# STPMXX.net
KiCad netlist of a schematic drawn in Altium Designer
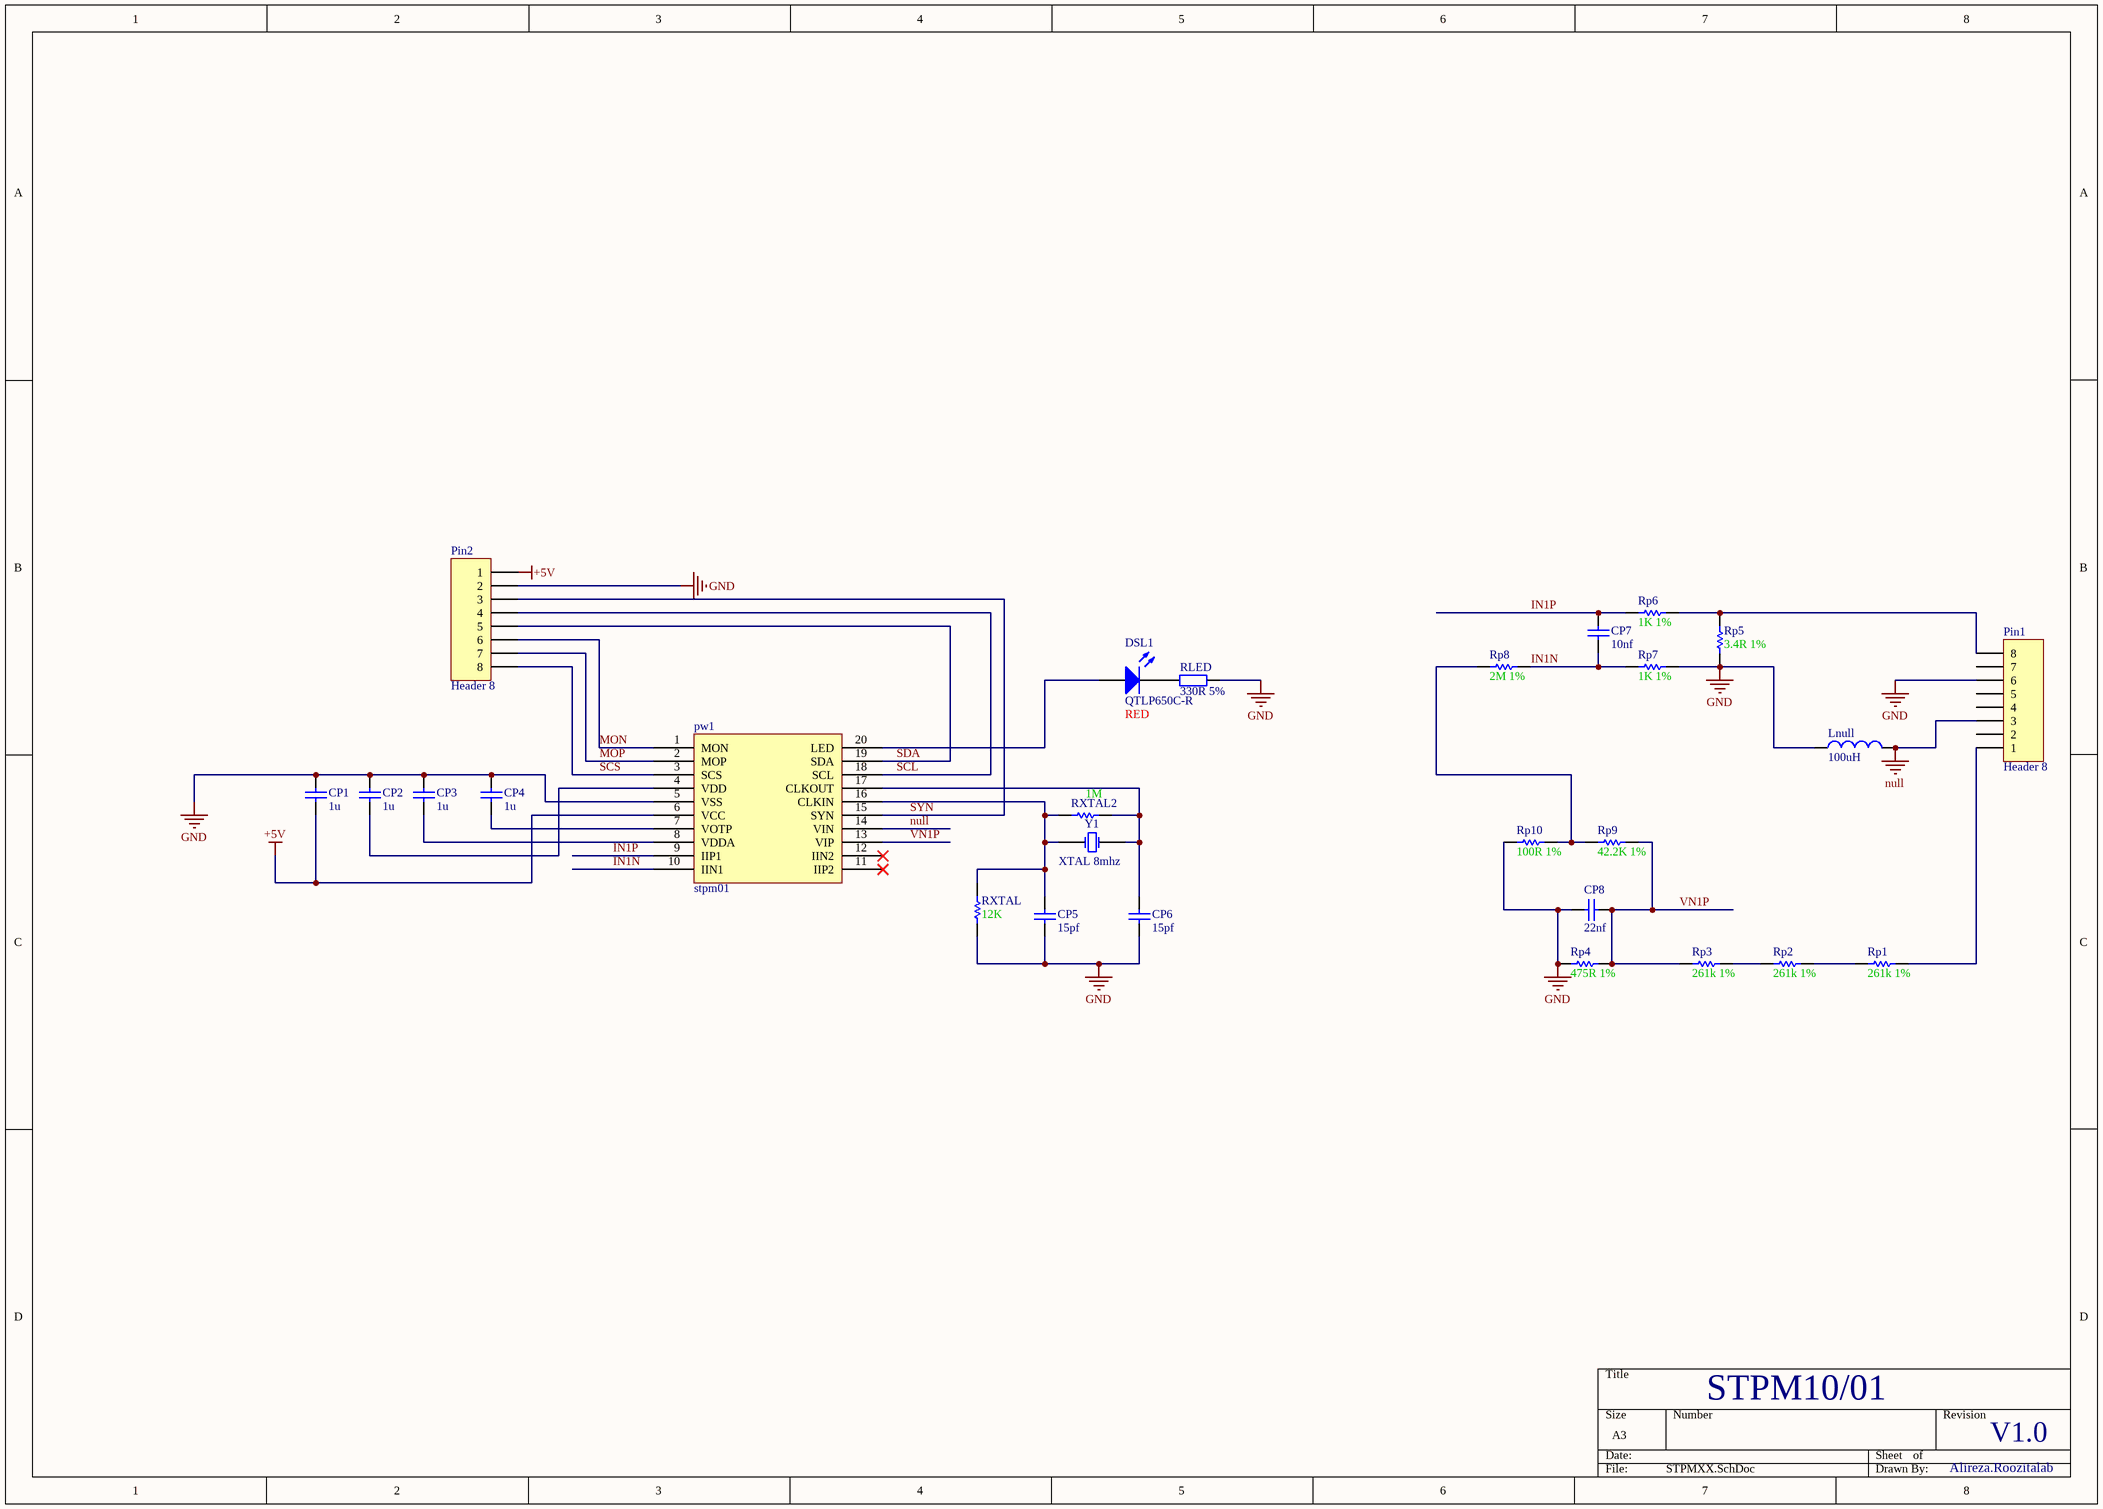
[diagram p0: STPMXX.SchDoc]

(export (version "E")
  (design (tool "Eeschema 10.0.6"))
  (components
    (comp (ref "CP1")
      (value "1u")
      (footprint "CAP 1206 (3216X08L)")
      (description "Capacitor")
      (fields (field (name "Comment") "Cap") (field (name "PUBLISHER") "Altium Limited"))
      (libsource (lib "alarmboxv2") (part "Cap"))
    )
    (comp (ref "CP2")
      (value "1u")
      (footprint "CAP 1206 (3216X08L)")
      (description "Capacitor")
      (fields (field (name "Comment") "Cap") (field (name "PUBLISHER") "Altium Limited"))
      (libsource (lib "alarmboxv2") (part "Cap"))
    )
    (comp (ref "CP3")
      (value "1u")
      (footprint "CAP 1206 (3216X08L)")
      (description "Capacitor")
      (fields (field (name "Comment") "Cap") (field (name "PUBLISHER") "Altium Limited"))
      (libsource (lib "alarmboxv2") (part "Cap"))
    )
    (comp (ref "CP4")
      (value "1u")
      (footprint "CAP 1206 (3216X08L)")
      (description "Capacitor")
      (fields (field (name "Comment") "Cap") (field (name "PUBLISHER") "Altium Limited"))
      (libsource (lib "alarmboxv2") (part "Cap"))
    )
    (comp (ref "CP5")
      (value "15pf")
      (footprint "CAP 1206 (3216X08L)")
      (description "Capacitor")
      (fields (field (name "Comment") "Cap") (field (name "PUBLISHER") "Altium Limited"))
      (libsource (lib "alarmboxv2") (part "Cap"))
    )
    (comp (ref "CP6")
      (value "15pf")
      (footprint "CAP 1206 (3216X08L)")
      (description "Capacitor")
      (fields (field (name "Comment") "Cap") (field (name "PUBLISHER") "Altium Limited"))
      (libsource (lib "alarmboxv2") (part "Cap"))
    )
    (comp (ref "CP7")
      (value "10nf")
      (footprint "CAP 1206 (3216X08L)")
      (description "Capacitor")
      (fields (field (name "Comment") "Cap") (field (name "PUBLISHER") "Altium Limited"))
      (libsource (lib "alarmboxv2") (part "Cap"))
    )
    (comp (ref "CP8")
      (value "22nf")
      (footprint "CAP 1206 (3216X08L)")
      (description "Capacitor")
      (fields (field (name "Comment") "Cap") (field (name "PUBLISHER") "Altium Limited"))
      (libsource (lib "alarmboxv2") (part "Cap"))
    )
    (comp (ref "DSL1")
      (value "QTLP650C-R")
      (footprint "led-1206")
      (description "Typical INFRARED GaAs LED")
      (fields (field (name "ALTIUM_VALUE") "RED") (field (name "PUBLISHER") "Altium Limited"))
      (libsource (lib "alarmboxv2") (part "LED0_1"))
    )
    (comp (ref "Lnull")
      (value "100uH")
      (footprint "INDUCTOR-1206")
      (description "Inductor")
      (fields (field (name "PUBLISHER") "Altium Limited"))
      (libsource (lib "alarmboxv2") (part "Inductor_1"))
    )
    (comp (ref "Pin1")
      (value "Header 8")
      (footprint "HDR1X8")
      (description "Header, 8-Pin")
      (fields (field (name "PUBLISHER") "Altium Limited"))
      (libsource (lib "") (part "Header 8_1"))
    )
    (comp (ref "Pin2")
      (value "Header 8")
      (footprint "HDR1X8")
      (description "Header, 8-Pin")
      (fields (field (name "PUBLISHER") "Altium Limited"))
      (libsource (lib "Miscellaneous Connectors") (part "Header 8"))
    )
    (comp (ref "pw1") (value "stpm01") (footprint "TSSOP") (libsource (lib "armlib") (part "stpm01")))
    (comp (ref "RLED")
      (value "330R 5%")
      (footprint "RES 1206 (3216X08L)")
      (description "Resistor")
      (fields (field (name "Comment") "Res2") (field (name "PUBLISHER") "Altium Limited"))
      (libsource (lib "alarmboxv2") (part "Res2_1"))
    )
    (comp (ref "Rp1")
      (value "261k 1%")
      (footprint "RES 1206 (3216X08L)")
      (description "Semiconductor Resistor")
      (fields (field (name "Comment") "Res Semi") (field (name "PUBLISHER") "Altium Limited"))
      (libsource (lib "alarmboxv2") (part "Res Semi"))
    )
    (comp (ref "Rp2")
      (value "261k 1%")
      (footprint "RES 1206 (3216X08L)")
      (description "Semiconductor Resistor")
      (fields (field (name "Comment") "Res Semi") (field (name "PUBLISHER") "Altium Limited"))
      (libsource (lib "alarmboxv2") (part "Res Semi"))
    )
    (comp (ref "Rp3")
      (value "261k 1%")
      (footprint "RES 1206 (3216X08L)")
      (description "Semiconductor Resistor")
      (fields (field (name "Comment") "Res Semi") (field (name "PUBLISHER") "Altium Limited"))
      (libsource (lib "alarmboxv2") (part "Res Semi"))
    )
    (comp (ref "Rp4")
      (value "475R 1%")
      (footprint "RES 1206 (3216X08L)")
      (description "Semiconductor Resistor")
      (fields (field (name "Comment") "Res Semi") (field (name "PUBLISHER") "Altium Limited"))
      (libsource (lib "alarmboxv2") (part "Res Semi"))
    )
    (comp (ref "Rp5")
      (value "3.4R 1%")
      (footprint "RES 1206 (3216X08L)")
      (description "Semiconductor Resistor")
      (fields (field (name "Comment") "Res Semi") (field (name "PUBLISHER") "Altium Limited"))
      (libsource (lib "alarmboxv2") (part "Res Semi"))
    )
    (comp (ref "Rp6")
      (value "1K 1%")
      (footprint "RES 1206 (3216X08L)")
      (description "Semiconductor Resistor")
      (fields (field (name "Comment") "Res Semi") (field (name "PUBLISHER") "Altium Limited"))
      (libsource (lib "alarmboxv2") (part "Res Semi"))
    )
    (comp (ref "Rp7")
      (value "1K 1%")
      (footprint "RES 1206 (3216X08L)")
      (description "Semiconductor Resistor")
      (fields (field (name "Comment") "Res Semi") (field (name "PUBLISHER") "Altium Limited"))
      (libsource (lib "alarmboxv2") (part "Res Semi"))
    )
    (comp (ref "Rp8")
      (value "2M 1%")
      (footprint "RES 1206 (3216X08L)")
      (description "Semiconductor Resistor")
      (fields (field (name "Comment") "Res Semi") (field (name "PUBLISHER") "Altium Limited"))
      (libsource (lib "alarmboxv2") (part "Res Semi"))
    )
    (comp (ref "Rp9")
      (value "42.2K 1%")
      (footprint "RES 1206 (3216X08L)")
      (description "Semiconductor Resistor")
      (fields (field (name "Comment") "Res Semi") (field (name "PUBLISHER") "Altium Limited"))
      (libsource (lib "alarmboxv2") (part "Res Semi"))
    )
    (comp (ref "Rp10")
      (value "100R 1%")
      (footprint "RES 1206 (3216X08L)")
      (description "Semiconductor Resistor")
      (fields (field (name "Comment") "Res Semi") (field (name "PUBLISHER") "Altium Limited"))
      (libsource (lib "alarmboxv2") (part "Res Semi"))
    )
    (comp (ref "RXTAL")
      (value "12K")
      (footprint "RES 1206 (3216X08L)")
      (description "Semiconductor Resistor")
      (fields (field (name "Comment") "Res Semi") (field (name "PUBLISHER") "Altium Limited"))
      (libsource (lib "alarmboxv2") (part "Res Semi"))
    )
    (comp (ref "RXTAL2")
      (value "1M")
      (footprint "RES 1206 (3216X08L)")
      (description "Semiconductor Resistor")
      (fields (field (name "Comment") "Res Semi") (field (name "PUBLISHER") "Altium Limited"))
      (libsource (lib "alarmboxv2") (part "Res Semi"))
    )
    (comp (ref "Y1")
      (value "XTAL 8mhz")
      (footprint "XTAL SMALL")
      (description "Crystal Oscillator")
      (fields (field (name "PUBLISHER") "Altium Limited"))
      (libsource (lib "alarmboxv2") (part "XTAL"))
    )
  )
  (nets
    (net (code "1") (name "+5V") (class "Default")
      (node (ref "CP1") (pin "1") (pinfunction "1_1") (pintype "passive"))
      (node (ref "Pin2") (pin "1") (pinfunction "1_1") (pintype "passive"))
      (node (ref "pw1") (pin "6") (pinfunction "VCC_6") (pintype "passive"))
    )
    (net (code "2") (name "/IN1N") (class "Default")
      (node (ref "CP7") (pin "1") (pinfunction "1_1") (pintype "passive"))
      (node (ref "Rp7") (pin "1") (pinfunction "1_1") (pintype "passive"))
      (node (ref "Rp8") (pin "2") (pinfunction "2_2") (pintype "passive"))
      (node (ref "pw1") (pin "10") (pinfunction "IIN1_10") (pintype "passive"))
    )
    (net (code "3") (name "/IN1P") (class "Default")
      (node (ref "CP7") (pin "2") (pinfunction "2_2") (pintype "passive"))
      (node (ref "Rp6") (pin "1") (pinfunction "1_1") (pintype "passive"))
      (node (ref "pw1") (pin "9") (pinfunction "IIP1_9") (pintype "passive"))
    )
    (net (code "4") (name "/MON") (class "Default")
      (node (ref "Pin2") (pin "6") (pinfunction "6_6") (pintype "passive"))
      (node (ref "pw1") (pin "1") (pinfunction "MON_1") (pintype "passive"))
    )
    (net (code "5") (name "/MOP") (class "Default")
      (node (ref "Pin2") (pin "7") (pinfunction "7_7") (pintype "passive"))
      (node (ref "pw1") (pin "2") (pinfunction "MOP_2") (pintype "passive"))
    )
    (net (code "6") (name "/SCL") (class "Default")
      (node (ref "Pin2") (pin "4") (pinfunction "4_4") (pintype "passive"))
      (node (ref "pw1") (pin "18") (pinfunction "SCL_18") (pintype "passive"))
    )
    (net (code "7") (name "/SCS") (class "Default")
      (node (ref "Pin2") (pin "8") (pinfunction "8_8") (pintype "passive"))
      (node (ref "pw1") (pin "3") (pinfunction "SCS_3") (pintype "passive"))
    )
    (net (code "8") (name "/SDA") (class "Default")
      (node (ref "Pin2") (pin "5") (pinfunction "5_5") (pintype "passive"))
      (node (ref "pw1") (pin "19") (pinfunction "SDA_19") (pintype "passive"))
    )
    (net (code "9") (name "/SYN") (class "Default")
      (node (ref "Pin2") (pin "3") (pinfunction "3_3") (pintype "passive"))
      (node (ref "pw1") (pin "15") (pinfunction "SYN_15") (pintype "passive"))
    )
    (net (code "10") (name "/VN1P") (class "Default")
      (node (ref "CP8") (pin "1") (pinfunction "1_1") (pintype "passive"))
      (node (ref "Rp3") (pin "2") (pinfunction "2_2") (pintype "passive"))
      (node (ref "Rp4") (pin "1") (pinfunction "1_1") (pintype "passive"))
      (node (ref "Rp9") (pin "2") (pinfunction "2_2") (pintype "passive"))
      (node (ref "pw1") (pin "13") (pinfunction "VIP_13") (pintype "passive"))
    )
    (net (code "11") (name "GND") (class "Default")
      (node (ref "CP1") (pin "2") (pinfunction "2_2") (pintype "passive"))
      (node (ref "CP2") (pin "2") (pinfunction "2_2") (pintype "passive"))
      (node (ref "CP3") (pin "2") (pinfunction "2_2") (pintype "passive"))
      (node (ref "CP4") (pin "2") (pinfunction "2_2") (pintype "passive"))
      (node (ref "CP5") (pin "1") (pinfunction "1_1") (pintype "passive"))
      (node (ref "CP6") (pin "1") (pinfunction "1_1") (pintype "passive"))
      (node (ref "CP8") (pin "2") (pinfunction "2_2") (pintype "passive"))
      (node (ref "Lnull") (pin "1") (pinfunction "1_1") (pintype "passive"))
      (node (ref "Pin1") (pin "6") (pinfunction "6_6") (pintype "passive"))
      (node (ref "Pin2") (pin "2") (pinfunction "2_2") (pintype "passive"))
      (node (ref "RLED") (pin "1") (pinfunction "1_1") (pintype "passive"))
      (node (ref "RXTAL") (pin "1") (pinfunction "1_1") (pintype "passive"))
      (node (ref "Rp10") (pin "1") (pinfunction "1_1") (pintype "passive"))
      (node (ref "Rp4") (pin "2") (pinfunction "2_2") (pintype "passive"))
      (node (ref "Rp5") (pin "1") (pinfunction "1_1") (pintype "passive"))
      (node (ref "Rp7") (pin "2") (pinfunction "2_2") (pintype "passive"))
      (node (ref "pw1") (pin "5") (pinfunction "VSS_5") (pintype "passive"))
    )
    (net (code "12") (name "Net-(DSL1-A)") (class "Default")
      (node (ref "DSL1") (pin "1") (pinfunction "A_1") (pintype "passive"))
      (node (ref "pw1") (pin "20") (pinfunction "LED_20") (pintype "passive"))
    )
    (net (code "13") (name "Net-(DSL1-K)") (class "Default")
      (node (ref "DSL1") (pin "2") (pinfunction "K_2") (pintype "passive"))
      (node (ref "RLED") (pin "2") (pinfunction "2_2") (pintype "passive"))
    )
    (net (code "14") (name "Net-(Pin1-Pad1)") (class "Default")
      (node (ref "Pin1") (pin "1") (pinfunction "1_1") (pintype "passive"))
      (node (ref "Rp1") (pin "1") (pinfunction "1_1") (pintype "passive"))
    )
    (net (code "15") (name "Net-(Pin1-Pad8)") (class "Default")
      (node (ref "Pin1") (pin "8") (pinfunction "8_8") (pintype "passive"))
      (node (ref "Rp5") (pin "2") (pinfunction "2_2") (pintype "passive"))
      (node (ref "Rp6") (pin "2") (pinfunction "2_2") (pintype "passive"))
    )
    (net (code "16") (name "Net-(Rp1-Pad2)") (class "Default")
      (node (ref "Rp1") (pin "2") (pinfunction "2_2") (pintype "passive"))
      (node (ref "Rp2") (pin "1") (pinfunction "1_1") (pintype "passive"))
    )
    (net (code "17") (name "Net-(Rp2-Pad2)") (class "Default")
      (node (ref "Rp2") (pin "2") (pinfunction "2_2") (pintype "passive"))
      (node (ref "Rp3") (pin "1") (pinfunction "1_1") (pintype "passive"))
    )
    (net (code "18") (name "Net-(Rp10-Pad2)") (class "Default")
      (node (ref "Rp10") (pin "2") (pinfunction "2_2") (pintype "passive"))
      (node (ref "Rp8") (pin "1") (pinfunction "1_1") (pintype "passive"))
      (node (ref "Rp9") (pin "1") (pinfunction "1_1") (pintype "passive"))
    )
    (net (code "19") (name "Net-(Y1-OSC1)") (class "Default")
      (node (ref "CP5") (pin "2") (pinfunction "2_2") (pintype "passive"))
      (node (ref "RXTAL") (pin "2") (pinfunction "2_2") (pintype "passive"))
      (node (ref "RXTAL2") (pin "2") (pinfunction "2_2") (pintype "passive"))
      (node (ref "Y1") (pin "1") (pinfunction "OSC1_1") (pintype "passive"))
      (node (ref "pw1") (pin "16") (pinfunction "CLKIN_16") (pintype "passive"))
    )
    (net (code "20") (name "Net-(Y1-OSC2)") (class "Default")
      (node (ref "CP6") (pin "2") (pinfunction "2_2") (pintype "passive"))
      (node (ref "RXTAL2") (pin "1") (pinfunction "1_1") (pintype "passive"))
      (node (ref "Y1") (pin "2") (pinfunction "OSC2_2") (pintype "passive"))
      (node (ref "pw1") (pin "17") (pinfunction "CLKOUT_17") (pintype "passive"))
    )
    (net (code "21") (name "Net-(pw1-VDD)") (class "Default")
      (node (ref "CP2") (pin "1") (pinfunction "1_1") (pintype "passive"))
      (node (ref "pw1") (pin "4") (pinfunction "VDD_4") (pintype "passive"))
    )
    (net (code "22") (name "Net-(pw1-VDDA)") (class "Default")
      (node (ref "CP3") (pin "1") (pinfunction "1_1") (pintype "passive"))
      (node (ref "pw1") (pin "8") (pinfunction "VDDA_8") (pintype "passive"))
    )
    (net (code "23") (name "Net-(pw1-VOTP)") (class "Default")
      (node (ref "CP4") (pin "1") (pinfunction "1_1") (pintype "passive"))
      (node (ref "pw1") (pin "7") (pinfunction "VOTP_7") (pintype "passive"))
    )
    (net (code "24") (name "null") (class "Default")
      (node (ref "Lnull") (pin "2") (pinfunction "2_2") (pintype "passive"))
      (node (ref "Pin1") (pin "3") (pinfunction "3_3") (pintype "passive"))
      (node (ref "pw1") (pin "14") (pinfunction "VIN_14") (pintype "passive"))
    )
    (net (code "25") (name "unconnected-(Pin1-Pad2)") (class "Default")
      (node (ref "Pin1") (pin "2") (pinfunction "2_2") (pintype "passive"))
    )
    (net (code "26") (name "unconnected-(Pin1-Pad4)") (class "Default")
      (node (ref "Pin1") (pin "4") (pinfunction "4_4") (pintype "passive"))
    )
    (net (code "27") (name "unconnected-(Pin1-Pad5)") (class "Default")
      (node (ref "Pin1") (pin "5") (pinfunction "5_5") (pintype "passive"))
    )
    (net (code "28") (name "unconnected-(Pin1-Pad7)") (class "Default")
      (node (ref "Pin1") (pin "7") (pinfunction "7_7") (pintype "passive"))
    )
    (net (code "29") (name "unconnected-(pw1-IIN2-Pad12)") (class "Default")
      (node (ref "pw1") (pin "12") (pinfunction "IIN2_12") (pintype "passive+no_connect"))
    )
    (net (code "30") (name "unconnected-(pw1-IIP2-Pad11)") (class "Default")
      (node (ref "pw1") (pin "11") (pinfunction "IIP2_11") (pintype "passive+no_connect"))
    )
  )
)
